# Display.net
KiCad netlist of a schematic drawn in Altium Designer
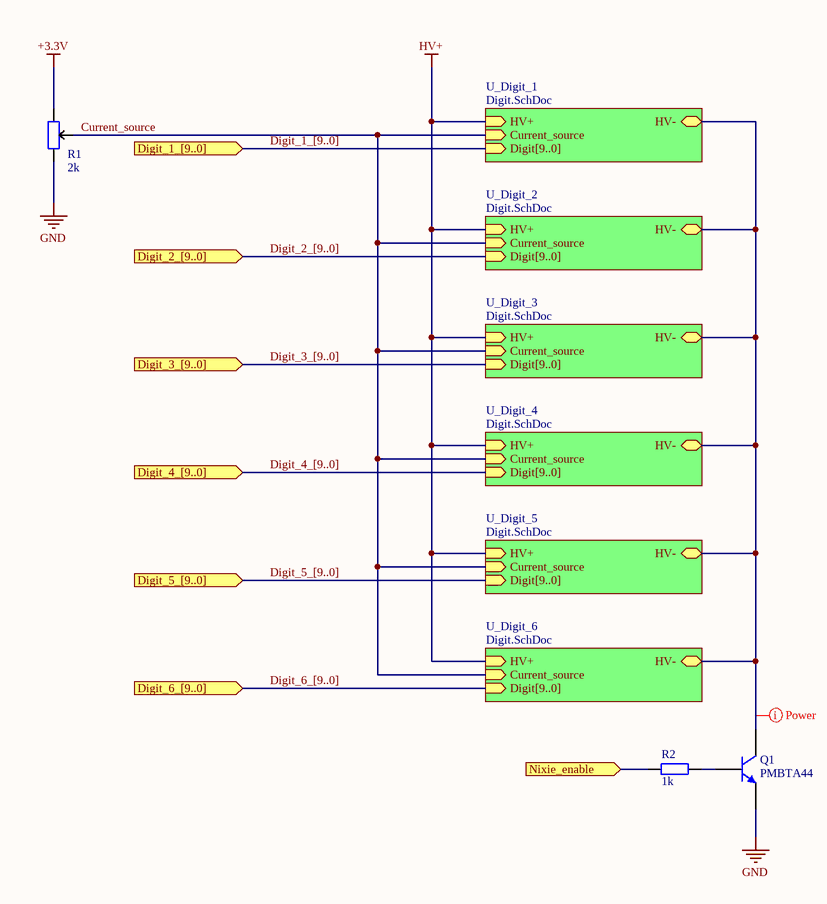
[diagram p0: Display.SchDoc]

(export (version "E")
  (design (tool "Eeschema 10.0.6"))
  (components
    (comp (ref "Q1")
      (value "PMBTA44")
      (footprint "SOT23_PMBTA44")
      (description "400 V, 0.3 A NPN high-voltage low VCEsat transistor")
      (libsource (lib "Nixie") (part "PMBTA44"))
    )
    (comp (ref "R1")
      (value "2k")
      (footprint "3314G-2-202E")
      (description "Trimming potentiometer, 2k")
      (libsource (lib "Nixie") (part "3314G-2-202E"))
    )
    (comp (ref "R2")
      (value "1k")
      (footprint "RES0805")
      (description "Chip resistor 1k 0805")
      (libsource (lib "Nixie") (part "1k 0805"))
    )
  )
  (nets
    (net (code "61") (name "+3.3V") (class "Default")
      (node (ref "R1") (pin "1") (pinfunction "1_1") (pintype "passive"))
    )
    (net (code "62") (name "/Current_source") (class "Default")
      (node (ref "R1") (pin "2") (pinfunction "2_2") (pintype "passive"))
    )
    (net (code "69") (name "/HV-") (class "Default")
      (node (ref "Q1") (pin "3") (pinfunction "C_3") (pintype "passive"))
    )
    (net (code "70") (name "/Nixie_enable") (class "Default")
      (node (ref "R2") (pin "1") (pinfunction "1_1") (pintype "passive"))
    )
    (net (code "71") (name "GND") (class "Default")
      (node (ref "Q1") (pin "2") (pinfunction "E_2") (pintype "passive"))
      (node (ref "R1") (pin "3") (pinfunction "3_3") (pintype "passive"))
    )
    (net (code "73") (name "Net-(Q1-B)") (class "Default")
      (node (ref "Q1") (pin "1") (pinfunction "B_1") (pintype "passive"))
      (node (ref "R2") (pin "2") (pinfunction "2_2") (pintype "passive"))
    )
  )
)
